# Sparkman_v2.net
KiCad netlist of a schematic drawn in EAGLE
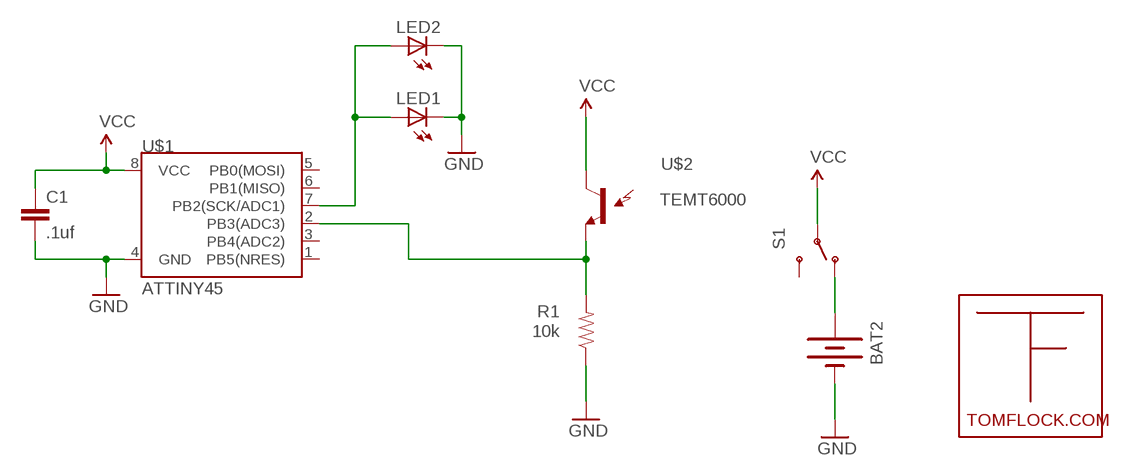
[diagram p0: schematic, sheet 1]

(export (version "E")
  (design (tool "Eeschema 10.0.6"))
  (components
    (comp (ref "BAT2")
      (value "BATTERY12MM")
      (footprint "eagle-import:BATTCON_12MM")
      (libsource (lib "eagle-import") (part "BATTERY12MM"))
    )
    (comp (ref "C1")
      (value ".1uf")
      (footprint "eagle-import:0603-CAP")
      (libsource (lib "eagle-import") (part "CAP0603-CAP"))
    )
    (comp (ref "LED1")
      (value "LED0603")
      (footprint "eagle-import:LED-0603")
      (libsource (lib "eagle-import") (part "LED0603"))
    )
    (comp (ref "LED2")
      (value "LED0603")
      (footprint "eagle-import:LED-0603")
      (libsource (lib "eagle-import") (part "LED0603"))
    )
    (comp (ref "R1")
      (value "10k")
      (footprint "eagle-import:0603-RES")
      (libsource (lib "eagle-import") (part "RESISTOR0603-RES"))
    )
    (comp (ref "S1")
      (value "SWITCH-SPSTSMD")
      (footprint "eagle-import:AYZ0202")
      (libsource (lib "eagle-import") (part "SWITCH-SPSTSMD"))
    )
    (comp (ref "U$1")
      (value "ATTINY45")
      (footprint "eagle-import:SO08-EIAJ")
      (libsource (lib "eagle-import") (part "ATTINY45"))
    )
    (comp (ref "U$2")
      (value "TEMT6000")
      (footprint "eagle-import:TEMT6000-SEN")
      (libsource (lib "eagle-import") (part "TEMT6000"))
    )
    (comp (ref "U$3")
      (value "TFLOGO")
      (footprint "eagle-import:TFLOGO")
      (libsource (lib "eagle-import") (part "TFLOGO"))
    )
  )
  (nets
    (net (code "1") (name "GND") (class "Default")
      (node (ref "BAT2") (pin "GND") (pinfunction "-_GND") (pintype "power_in"))
      (node (ref "C1") (pin "2") (pinfunction "2_2") (pintype "passive"))
      (node (ref "LED1") (pin "C") (pinfunction "C_C") (pintype "passive"))
      (node (ref "LED2") (pin "C") (pinfunction "C_C") (pintype "passive"))
      (node (ref "R1") (pin "1") (pinfunction "1_1") (pintype "passive"))
      (node (ref "U$1") (pin "4") (pinfunction "GND_4") (pintype "bidirectional"))
    )
    (net (code "2") (name "Net-(BAT2-+)") (class "Default")
      (node (ref "BAT2") (pin "PWR@1") (pinfunction "+_PWR@1") (pintype "power_in"))
      (node (ref "S1") (pin "1") (pinfunction "O_1") (pintype "passive"))
    )
    (net (code "3") (name "Net-(U$1-PB2(SCK{slash}ADC1))") (class "Default")
      (node (ref "LED1") (pin "A") (pinfunction "A_A") (pintype "passive"))
      (node (ref "LED2") (pin "A") (pinfunction "A_A") (pintype "passive"))
      (node (ref "U$1") (pin "7") (pinfunction "PB2(SCK/ADC1)_7") (pintype "bidirectional"))
    )
    (net (code "4") (name "Net-(U$1-PB3(ADC3))") (class "Default")
      (node (ref "R1") (pin "2") (pinfunction "2_2") (pintype "passive"))
      (node (ref "U$1") (pin "2") (pinfunction "PB3(ADC3)_2") (pintype "bidirectional"))
      (node (ref "U$2") (pin "EMITTER") (pinfunction "E1_EMITTER") (pintype "passive"))
    )
    (net (code "5") (name "VCC") (class "Default")
      (node (ref "C1") (pin "1") (pinfunction "1_1") (pintype "passive"))
      (node (ref "S1") (pin "2") (pinfunction "P_2") (pintype "passive"))
      (node (ref "U$1") (pin "8") (pinfunction "VCC_8") (pintype "bidirectional"))
      (node (ref "U$2") (pin "COLLECTOR") (pinfunction "C1_COLLECTOR") (pintype "passive"))
    )
    (net (code "6") (name "unconnected-(S1-S-Pad3)") (class "Default")
      (node (ref "S1") (pin "3") (pinfunction "S_3") (pintype "passive"))
    )
    (net (code "7") (name "unconnected-(U$1-PB0(MOSI)-Pad5)") (class "Default")
      (node (ref "U$1") (pin "5") (pinfunction "PB0(MOSI)_5") (pintype "bidirectional"))
    )
    (net (code "8") (name "unconnected-(U$1-PB1(MISO)-Pad6)") (class "Default")
      (node (ref "U$1") (pin "6") (pinfunction "PB1(MISO)_6") (pintype "bidirectional"))
    )
    (net (code "9") (name "unconnected-(U$1-PB4(ADC2)-Pad3)") (class "Default")
      (node (ref "U$1") (pin "3") (pinfunction "PB4(ADC2)_3") (pintype "bidirectional"))
    )
    (net (code "10") (name "unconnected-(U$1-PB5(NRES)-Pad1)") (class "Default")
      (node (ref "U$1") (pin "1") (pinfunction "PB5(NRES)_1") (pintype "bidirectional"))
    )
  )
)
